# dip16breakout.net
KiCad netlist of a schematic drawn in EAGLE
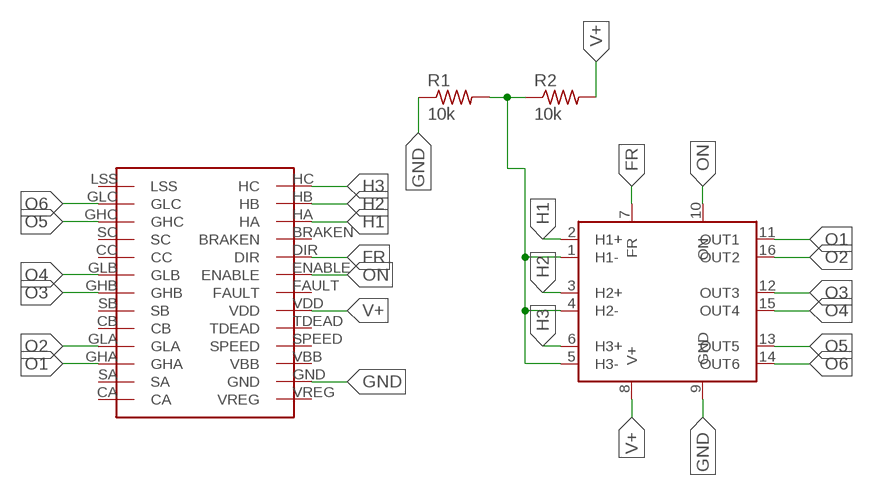
[diagram p0: schematic, sheet 1]

(export (version "E")
  (design (tool "Eeschema 10.0.6"))
  (components
    (comp (ref "R1")
      (value "10k")
      (footprint "eagle-import:R0805")
      (libsource (lib "eagle-import") (part "R-US_R0805"))
    )
    (comp (ref "R2")
      (value "10k")
      (footprint "eagle-import:R0805")
      (libsource (lib "eagle-import") (part "R-US_R0805"))
    )
    (comp (ref "U$1")
      (value "NJM2624A")
      (footprint "eagle-import:DMP16")
      (libsource (lib "eagle-import") (part "NJM2624A"))
    )
    (comp (ref "U$2")
      (value "TSSOP28-BRK")
      (footprint "eagle-import:TSSOP28-BRK")
      (libsource (lib "eagle-import") (part "TSSOP28-BRK"))
    )
  )
  (nets
    (net (code "1") (name "FR") (class "Default")
      (node (ref "U$1") (pin "7") (pinfunction "FR_7") (pintype "bidirectional"))
      (node (ref "U$2") (pin "DIR") (pinfunction "DIR_DIR") (pintype "bidirectional"))
    )
    (net (code "2") (name "GND") (class "Default")
      (node (ref "R1") (pin "1") (pinfunction "1_1") (pintype "passive"))
      (node (ref "U$1") (pin "9") (pinfunction "GND_9") (pintype "bidirectional"))
      (node (ref "U$2") (pin "GND") (pinfunction "GND_GND") (pintype "bidirectional"))
    )
    (net (code "3") (name "H1") (class "Default")
      (node (ref "U$1") (pin "2") (pinfunction "H1+_2") (pintype "bidirectional"))
      (node (ref "U$2") (pin "HA") (pinfunction "HA_HA") (pintype "bidirectional"))
    )
    (net (code "4") (name "H2") (class "Default")
      (node (ref "U$1") (pin "3") (pinfunction "H2+_3") (pintype "bidirectional"))
      (node (ref "U$2") (pin "HB") (pinfunction "HB_HB") (pintype "bidirectional"))
    )
    (net (code "5") (name "H3") (class "Default")
      (node (ref "U$1") (pin "6") (pinfunction "H3+_6") (pintype "bidirectional"))
      (node (ref "U$2") (pin "HC") (pinfunction "HC_HC") (pintype "bidirectional"))
    )
    (net (code "6") (name "Net-(U$1-H1-)") (class "Default")
      (node (ref "R1") (pin "2") (pinfunction "2_2") (pintype "passive"))
      (node (ref "R2") (pin "1") (pinfunction "1_1") (pintype "passive"))
      (node (ref "U$1") (pin "1") (pinfunction "H1-_1") (pintype "bidirectional"))
      (node (ref "U$1") (pin "4") (pinfunction "H2-_4") (pintype "bidirectional"))
      (node (ref "U$1") (pin "5") (pinfunction "H3-_5") (pintype "bidirectional"))
    )
    (net (code "7") (name "O1") (class "Default")
      (node (ref "U$1") (pin "11") (pinfunction "OUT1_11") (pintype "bidirectional"))
      (node (ref "U$2") (pin "GHA") (pinfunction "GHA_GHA") (pintype "bidirectional"))
    )
    (net (code "8") (name "O2") (class "Default")
      (node (ref "U$1") (pin "16") (pinfunction "OUT2_16") (pintype "bidirectional"))
      (node (ref "U$2") (pin "GLA") (pinfunction "GLA_GLA") (pintype "bidirectional"))
    )
    (net (code "9") (name "O3") (class "Default")
      (node (ref "U$1") (pin "12") (pinfunction "OUT3_12") (pintype "bidirectional"))
      (node (ref "U$2") (pin "GHB") (pinfunction "GHB_GHB") (pintype "bidirectional"))
    )
    (net (code "10") (name "O4") (class "Default")
      (node (ref "U$1") (pin "15") (pinfunction "OUT4_15") (pintype "bidirectional"))
      (node (ref "U$2") (pin "GLB") (pinfunction "GLB_GLB") (pintype "bidirectional"))
    )
    (net (code "11") (name "O5") (class "Default")
      (node (ref "U$1") (pin "13") (pinfunction "OUT5_13") (pintype "bidirectional"))
      (node (ref "U$2") (pin "GHC") (pinfunction "GHC_GHC") (pintype "bidirectional"))
    )
    (net (code "12") (name "O6") (class "Default")
      (node (ref "U$1") (pin "14") (pinfunction "OUT6_14") (pintype "bidirectional"))
      (node (ref "U$2") (pin "GLC") (pinfunction "GLC_GLC") (pintype "bidirectional"))
    )
    (net (code "13") (name "ON") (class "Default")
      (node (ref "U$1") (pin "10") (pinfunction "ON_10") (pintype "bidirectional"))
      (node (ref "U$2") (pin "ENABLE") (pinfunction "ENABLE_ENABLE") (pintype "bidirectional"))
    )
    (net (code "14") (name "V+") (class "Default")
      (node (ref "R2") (pin "2") (pinfunction "2_2") (pintype "passive"))
      (node (ref "U$1") (pin "8") (pinfunction "V+_8") (pintype "bidirectional"))
      (node (ref "U$2") (pin "VDD") (pinfunction "VDD_VDD") (pintype "bidirectional"))
    )
    (net (code "15") (name "unconnected-(U$2-PadBRAKEN)") (class "Default")
      (node (ref "U$2") (pin "BRAKEN") (pinfunction "BRAKEN_BRAKEN") (pintype "bidirectional"))
    )
    (net (code "16") (name "unconnected-(U$2-PadCA)") (class "Default")
      (node (ref "U$2") (pin "CA") (pinfunction "CA_CA") (pintype "bidirectional"))
    )
    (net (code "17") (name "unconnected-(U$2-PadCB)") (class "Default")
      (node (ref "U$2") (pin "CB") (pinfunction "CB_CB") (pintype "bidirectional"))
    )
    (net (code "18") (name "unconnected-(U$2-PadCC)") (class "Default")
      (node (ref "U$2") (pin "CC") (pinfunction "CC_CC") (pintype "bidirectional"))
    )
    (net (code "19") (name "unconnected-(U$2-PadFAULT)") (class "Default")
      (node (ref "U$2") (pin "FAULT") (pinfunction "FAULT_FAULT") (pintype "bidirectional"))
    )
    (net (code "20") (name "unconnected-(U$2-PadLSS)") (class "Default")
      (node (ref "U$2") (pin "LSS") (pinfunction "LSS_LSS") (pintype "bidirectional"))
    )
    (net (code "21") (name "unconnected-(U$2-PadSA)") (class "Default")
      (node (ref "U$2") (pin "SA") (pinfunction "SA_SA") (pintype "bidirectional"))
    )
    (net (code "22") (name "unconnected-(U$2-PadSB)") (class "Default")
      (node (ref "U$2") (pin "SB") (pinfunction "SB_SB") (pintype "bidirectional"))
    )
    (net (code "23") (name "unconnected-(U$2-PadSC)") (class "Default")
      (node (ref "U$2") (pin "SC") (pinfunction "SC_SC") (pintype "bidirectional"))
    )
    (net (code "24") (name "unconnected-(U$2-PadSPEED)") (class "Default")
      (node (ref "U$2") (pin "SPEED") (pinfunction "SPEED_SPEED") (pintype "bidirectional"))
    )
    (net (code "25") (name "unconnected-(U$2-PadTDEAD)") (class "Default")
      (node (ref "U$2") (pin "TDEAD") (pinfunction "TDEAD_TDEAD") (pintype "bidirectional"))
    )
    (net (code "26") (name "unconnected-(U$2-PadVBB)") (class "Default")
      (node (ref "U$2") (pin "VBB") (pinfunction "VBB_VBB") (pintype "bidirectional"))
    )
    (net (code "27") (name "unconnected-(U$2-PadVREG)") (class "Default")
      (node (ref "U$2") (pin "VREG") (pinfunction "VREG_VREG") (pintype "bidirectional"))
    )
  )
)
